# SCH_ESP32-S3-DevKitC-1_2026-10-10_1.net
KiCad netlist of a schematic drawn in EasyEDA
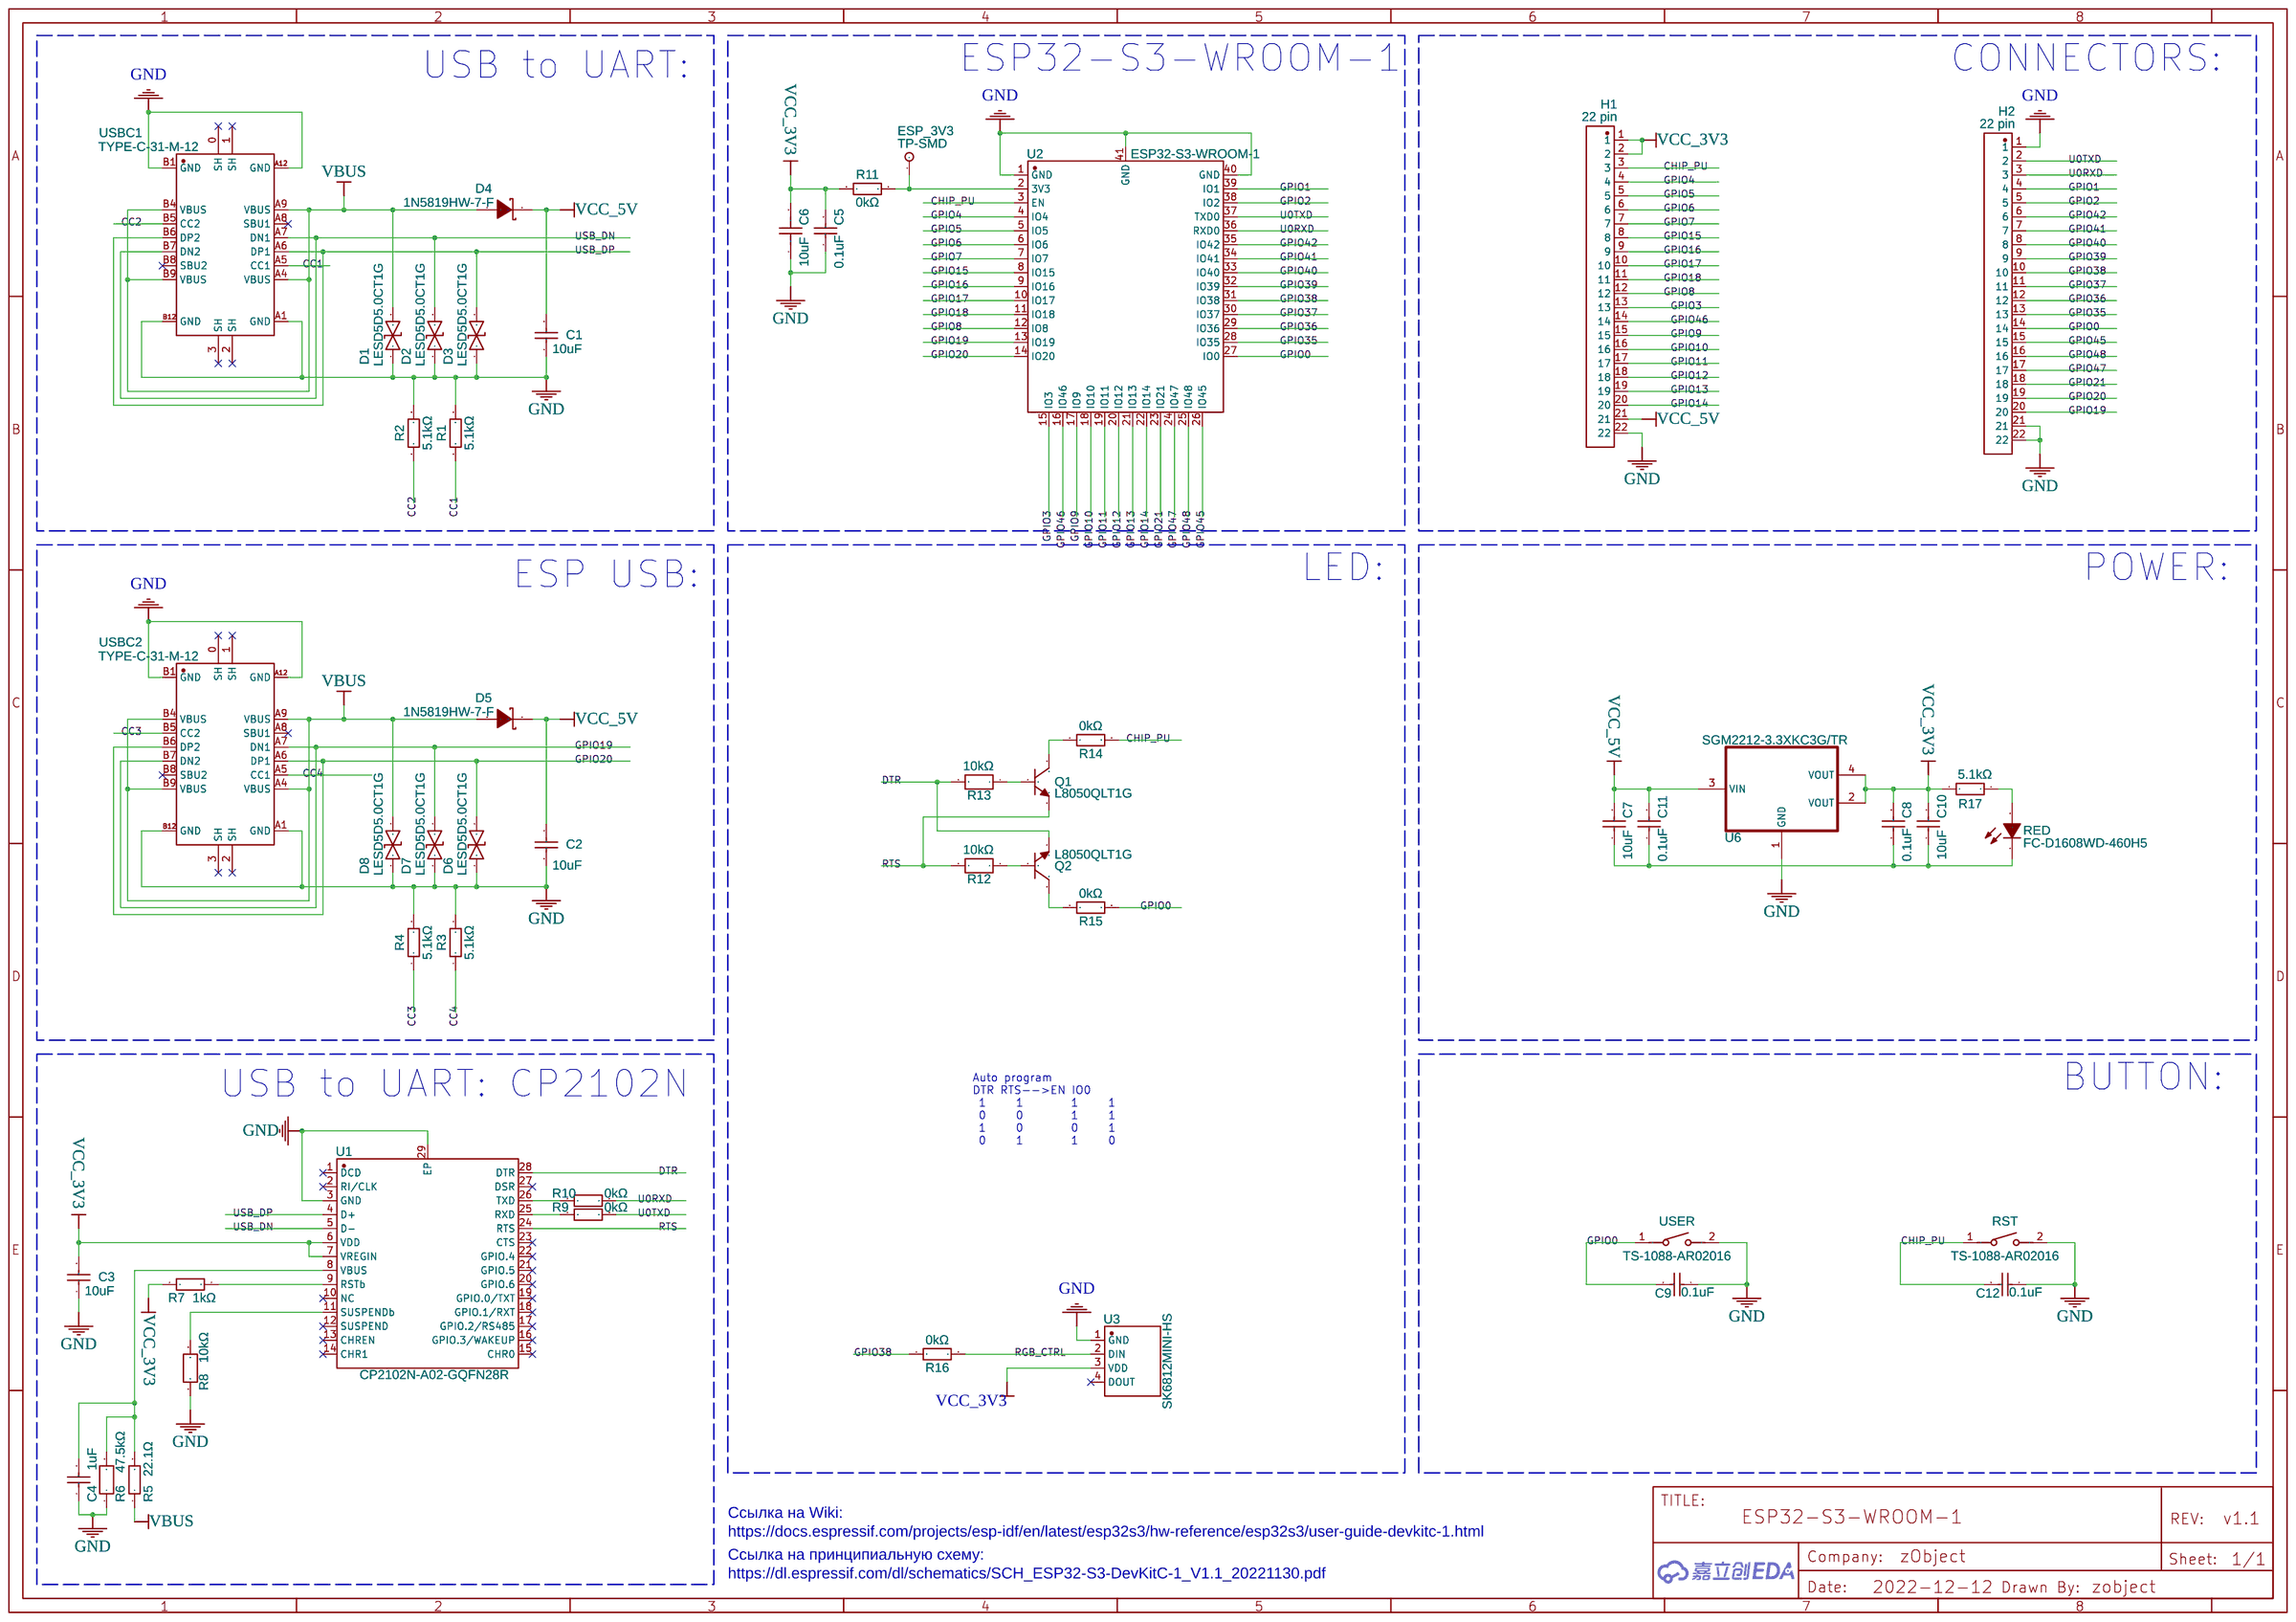
[diagram p0: schematic sheet]

(export (version "E")
  (design (tool "Eeschema 10.0.6"))
  (components
    (comp (ref "C1")
      (value "10uF")
      (fields (field (name "Manufacturer Part") "0603F106M160NT") (field (name "Manufacturer") "FH"))
      (libsource (lib "") (part "0603F106M160NT"))
    )
    (comp (ref "C2")
      (value "10uF")
      (fields (field (name "Manufacturer Part") "0603F106M160NT") (field (name "Manufacturer") "FH"))
      (libsource (lib "") (part "0603F106M160NT"))
    )
    (comp (ref "C3")
      (value "10uF")
      (fields (field (name "Manufacturer Part") "0603F106M160NT") (field (name "Manufacturer") "FH"))
      (libsource (lib "") (part "0603F106M160NT"))
    )
    (comp (ref "C4")
      (value "1uF")
      (fields (field (name "Manufacturer Part") "C1608X5R1C105KT000N") (field (name "Manufacturer") "TDK"))
      (libsource (lib "") (part "C1608X5R1C105KT000N"))
    )
    (comp (ref "C5")
      (value "0.1uF")
      (fields (field (name "Manufacturer Part") "0603B104K500NT") (field (name "Manufacturer") "FH(风华)"))
      (libsource (lib "") (part "0603B104K500NT"))
    )
    (comp (ref "C6")
      (value "10uF")
      (fields
        (field (name "Manufacturer Part") "LMK107BJ106MALTD")
        (field (name "Manufacturer") "TAIYO YUDEN")
      )
      (libsource (lib "") (part "LMK107BJ106MALTD"))
    )
    (comp (ref "C7")
      (value "10uF")
      (fields (field (name "Manufacturer Part") "0603F106M160NT") (field (name "Manufacturer") "FH"))
      (libsource (lib "") (part "0603F106M160NT"))
    )
    (comp (ref "C8")
      (value "0.1uF")
      (fields (field (name "Manufacturer Part") "0603B104K500NT") (field (name "Manufacturer") "FH(风华)"))
      (libsource (lib "") (part "0603B104K500NT"))
    )
    (comp (ref "C9")
      (value "0.1uF")
      (fields (field (name "Manufacturer Part") "0603B104K500NT") (field (name "Manufacturer") "FH(风华)"))
      (libsource (lib "") (part "0603B104K500NT_1"))
    )
    (comp (ref "C10")
      (value "10uF")
      (fields (field (name "Manufacturer Part") "0603F106M160NT") (field (name "Manufacturer") "FH"))
      (libsource (lib "") (part "0603F106M160NT"))
    )
    (comp (ref "C11")
      (value "0.1uF")
      (fields (field (name "Manufacturer Part") "0603B104K500NT") (field (name "Manufacturer") "FH(风华)"))
      (libsource (lib "") (part "0603B104K500NT"))
    )
    (comp (ref "C12")
      (value "0.1uF")
      (fields (field (name "Manufacturer Part") "0603B104K500NT") (field (name "Manufacturer") "FH(风华)"))
      (libsource (lib "") (part "0603B104K500NT_1"))
    )
    (comp (ref "D1")
      (value "LESD5D5.0CT1G")
      (fields (field (name "Manufacturer") "Leshan Radio"))
      (libsource (lib "") (part "LESD5D5.0CT1G"))
    )
    (comp (ref "D2")
      (value "LESD5D5.0CT1G")
      (fields (field (name "Manufacturer") "Leshan Radio"))
      (libsource (lib "") (part "LESD5D5.0CT1G"))
    )
    (comp (ref "D3")
      (value "LESD5D5.0CT1G")
      (fields (field (name "Manufacturer") "Leshan Radio"))
      (libsource (lib "") (part "LESD5D5.0CT1G"))
    )
    (comp (ref "D4")
      (value "1N5819HW-7-F")
      (fields (field (name "Manufacturer") "DIODES(美台)"))
      (libsource (lib "") (part "1N5819HW-7-F"))
    )
    (comp (ref "D5")
      (value "1N5819HW-7-F")
      (fields (field (name "Manufacturer") "DIODES(美台)"))
      (libsource (lib "") (part "1N5819HW-7-F"))
    )
    (comp (ref "D6")
      (value "LESD5D5.0CT1G")
      (fields (field (name "Manufacturer") "Leshan Radio"))
      (libsource (lib "") (part "LESD5D5.0CT1G"))
    )
    (comp (ref "D7")
      (value "LESD5D5.0CT1G")
      (fields (field (name "Manufacturer") "Leshan Radio"))
      (libsource (lib "") (part "LESD5D5.0CT1G"))
    )
    (comp (ref "D8")
      (value "LESD5D5.0CT1G")
      (fields (field (name "Manufacturer") "Leshan Radio"))
      (libsource (lib "") (part "LESD5D5.0CT1G"))
    )
    (comp (ref "ESP_3V3") (value "TP-SMD") (libsource (lib "") (part "TP-SMD")))
    (comp (ref "H1")
      (value "22 pin")
      (fields (field (name "Manufacturer Part") "22850120ANG1SYA01") (field (name "Manufacturer") "JILN(锦凌)"))
      (libsource (lib "") (part "22 pin"))
    )
    (comp (ref "H2")
      (value "22 pin")
      (fields (field (name "Manufacturer Part") "22850120ANG1SYA01") (field (name "Manufacturer") "JILN(锦凌)"))
      (libsource (lib "") (part "22 pin"))
    )
    (comp (ref "Q1")
      (value "L8050QLT1G")
      (fields (field (name "Manufacturer") "LRC(乐山无线电)"))
      (libsource (lib "") (part "L8050QLT1G_1"))
    )
    (comp (ref "Q2")
      (value "L8050QLT1G")
      (fields (field (name "Manufacturer") "LRC(乐山无线电)"))
      (libsource (lib "") (part "L8050QLT1G"))
    )
    (comp (ref "R1")
      (value "5.1kΩ")
      (fields (field (name "Manufacturer Part") "RTT035101BTP") (field (name "Manufacturer") "RALEC(旺诠)"))
      (libsource (lib "") (part "RTT035101BTP"))
    )
    (comp (ref "R2")
      (value "5.1kΩ")
      (fields (field (name "Manufacturer Part") "RTT035101BTP") (field (name "Manufacturer") "RALEC(旺诠)"))
      (libsource (lib "") (part "RTT035101BTP"))
    )
    (comp (ref "R3")
      (value "5.1kΩ")
      (fields (field (name "Manufacturer Part") "RTT035101BTP") (field (name "Manufacturer") "RALEC(旺诠)"))
      (libsource (lib "") (part "RTT035101BTP"))
    )
    (comp (ref "R4")
      (value "5.1kΩ")
      (fields (field (name "Manufacturer Part") "RTT035101BTP") (field (name "Manufacturer") "RALEC(旺诠)"))
      (libsource (lib "") (part "RTT035101BTP"))
    )
    (comp (ref "R5")
      (value "22.1Ω")
      (fields (field (name "Manufacturer Part") "RCT0322R1FLF") (field (name "Manufacturer") "HKR"))
      (libsource (lib "") (part "RCT0322R1FLF"))
    )
    (comp (ref "R6")
      (value "47.5kΩ")
      (fields (field (name "Manufacturer Part") "ERJPB3B4752V") (field (name "Manufacturer") "PANASONIC(松下)"))
      (libsource (lib "") (part "ERJPB3B4752V"))
    )
    (comp (ref "R7")
      (value "1kΩ")
      (fields (field (name "Manufacturer Part") "RN73H1JTTD1001B25") (field (name "Manufacturer") "KOA"))
      (libsource (lib "") (part "RN73H1JTTD1001B25"))
    )
    (comp (ref "R8")
      (value "10kΩ")
      (fields (field (name "Manufacturer Part") "CR-03JA7---10K") (field (name "Manufacturer") "Viking(光颉)"))
      (libsource (lib "") (part "CR-03JA7---10K_1"))
    )
    (comp (ref "R9")
      (value "0kΩ")
      (fields (field (name "Manufacturer Part") "RN73H1JTTD1001B25") (field (name "Manufacturer") "KOA"))
      (libsource (lib "") (part "RN73H1JTTD1001B25"))
    )
    (comp (ref "R10")
      (value "0kΩ")
      (fields (field (name "Manufacturer Part") "RN73H1JTTD1001B25") (field (name "Manufacturer") "KOA"))
      (libsource (lib "") (part "RN73H1JTTD1001B25"))
    )
    (comp (ref "R11")
      (value "0kΩ")
      (fields (field (name "Manufacturer Part") "RN73H1JTTD1001B25") (field (name "Manufacturer") "KOA"))
      (libsource (lib "") (part "RN73H1JTTD1001B25"))
    )
    (comp (ref "R12")
      (value "10kΩ")
      (fields (field (name "Manufacturer Part") "CR-03JA7---10K") (field (name "Manufacturer") "Viking(光颉)"))
      (libsource (lib "") (part "CR-03JA7---10K"))
    )
    (comp (ref "R13")
      (value "10kΩ")
      (fields (field (name "Manufacturer Part") "CR-03JA7---10K") (field (name "Manufacturer") "Viking(光颉)"))
      (libsource (lib "") (part "CR-03JA7---10K"))
    )
    (comp (ref "R14")
      (value "0kΩ")
      (fields (field (name "Manufacturer Part") "RN73H1JTTD1001B25") (field (name "Manufacturer") "KOA"))
      (libsource (lib "") (part "RN73H1JTTD1001B25"))
    )
    (comp (ref "R15")
      (value "0kΩ")
      (fields (field (name "Manufacturer Part") "RN73H1JTTD1001B25") (field (name "Manufacturer") "KOA"))
      (libsource (lib "") (part "RN73H1JTTD1001B25"))
    )
    (comp (ref "R16")
      (value "0kΩ")
      (fields (field (name "Manufacturer Part") "RN73H1JTTD1001B25") (field (name "Manufacturer") "KOA"))
      (libsource (lib "") (part "RN73H1JTTD1001B25"))
    )
    (comp (ref "R17")
      (value "5.1kΩ")
      (fields (field (name "Manufacturer Part") "RTT035101BTP") (field (name "Manufacturer") "RALEC(旺诠)"))
      (libsource (lib "") (part "RTT035101BTP_1"))
    )
    (comp (ref "RED")
      (value "FC-D1608WD-460H5")
      (fields (field (name "Manufacturer Part") "NCD0603W1") (field (name "Manufacturer") "国星光电"))
      (libsource (lib "") (part "FC-D1608WD-460H5"))
    )
    (comp (ref "RST")
      (value "TS-1088-AR02016")
      (fields (field (name "Manufacturer") "XUNPU(讯普)"))
      (libsource (lib "") (part "TS-1088-AR02016"))
    )
    (comp (ref "U1")
      (value "CP2102N-A02-GQFN28R")
      (fields (field (name "Manufacturer") "SILICON LABS(芯科)"))
      (libsource (lib "") (part "CP2102N-A02-GQFN28R"))
    )
    (comp (ref "U2")
      (value "ESP32-S3-WROOM-1")
      (fields
        (field (name "Manufacturer Part") "ESP32-S3-WROOM-1(N8R8)")
        (field (name "Manufacturer") "ESPRESSIF(乐鑫)")
      )
      (libsource (lib "") (part "ESP32-S3-WROOM-1(N8R8)"))
    )
    (comp (ref "U3") (value "SK6812MINI-HS") (libsource (lib "") (part "SK6812MINI-HS")))
    (comp (ref "U6") (value "SGM2212-3.3XKC3G/TR") (libsource (lib "") (part "SGM2212-3.3XKC3G/TR")))
    (comp (ref "USBC1")
      (value "TYPE-C-31-M-12")
      (fields (field (name "Manufacturer") "韩国韩荣"))
      (libsource (lib "") (part "TYPE-C-31-M-12"))
    )
    (comp (ref "USBC2")
      (value "TYPE-C-31-M-12")
      (fields (field (name "Manufacturer") "韩国韩荣"))
      (libsource (lib "") (part "TYPE-C-31-M-12"))
    )
    (comp (ref "USER")
      (value "TS-1088-AR02016")
      (fields (field (name "Manufacturer") "XUNPU(讯普)"))
      (libsource (lib "") (part "TS-1088-AR02016_1"))
    )
  )
  (nets
    (net (code "1") (name "/CC1") (class "Default")
      (node (ref "R1") (pin "1") (pinfunction "1_1") (pintype "unspecified"))
      (node (ref "USBC1") (pin "A5") (pinfunction "CC1_A5") (pintype "unspecified"))
    )
    (net (code "2") (name "/CC2") (class "Default")
      (node (ref "R2") (pin "1") (pinfunction "1_1") (pintype "unspecified"))
      (node (ref "USBC1") (pin "B5") (pinfunction "CC2_B5") (pintype "unspecified"))
    )
    (net (code "3") (name "/CC3") (class "Default")
      (node (ref "R4") (pin "1") (pinfunction "1_1") (pintype "unspecified"))
      (node (ref "USBC2") (pin "B5") (pinfunction "CC2_B5") (pintype "unspecified"))
    )
    (net (code "4") (name "/CC4") (class "Default")
      (node (ref "R3") (pin "1") (pinfunction "1_1") (pintype "unspecified"))
      (node (ref "USBC2") (pin "A5") (pinfunction "CC1_A5") (pintype "unspecified"))
    )
    (net (code "5") (name "/CHIP_PU") (class "Default")
      (node (ref "C12") (pin "2") (pinfunction "2_2") (pintype "input"))
      (node (ref "H1") (pin "3") (pinfunction "3_3") (pintype "unspecified"))
      (node (ref "R14") (pin "2") (pinfunction "2_2") (pintype "unspecified"))
      (node (ref "RST") (pin "1") (pinfunction "1_1") (pintype "unspecified"))
      (node (ref "U2") (pin "3") (pinfunction "EN_3") (pintype "unspecified"))
    )
    (net (code "6") (name "/DTR") (class "Default")
      (node (ref "Q2") (pin "2") (pinfunction "E_2") (pintype "unspecified"))
      (node (ref "R13") (pin "2") (pinfunction "2_2") (pintype "unspecified"))
      (node (ref "U1") (pin "28") (pinfunction "DTR_28") (pintype "unspecified"))
    )
    (net (code "7") (name "/GPIO0") (class "Default")
      (node (ref "C9") (pin "2") (pinfunction "2_2") (pintype "input"))
      (node (ref "H2") (pin "14") (pinfunction "14_14") (pintype "unspecified"))
      (node (ref "R15") (pin "2") (pinfunction "2_2") (pintype "unspecified"))
      (node (ref "U2") (pin "27") (pinfunction "IO0_27") (pintype "unspecified"))
      (node (ref "USER") (pin "1") (pinfunction "1_1") (pintype "unspecified"))
    )
    (net (code "8") (name "/GPIO1") (class "Default")
      (node (ref "H2") (pin "4") (pinfunction "4_4") (pintype "unspecified"))
      (node (ref "U2") (pin "39") (pinfunction "IO1_39") (pintype "unspecified"))
    )
    (net (code "9") (name "/GPIO2") (class "Default")
      (node (ref "H2") (pin "5") (pinfunction "5_5") (pintype "unspecified"))
      (node (ref "U2") (pin "38") (pinfunction "IO2_38") (pintype "unspecified"))
    )
    (net (code "10") (name "/GPIO3") (class "Default")
      (node (ref "H1") (pin "13") (pinfunction "13_13") (pintype "unspecified"))
      (node (ref "U2") (pin "15") (pinfunction "IO3_15") (pintype "unspecified"))
    )
    (net (code "11") (name "/GPIO4") (class "Default")
      (node (ref "H1") (pin "4") (pinfunction "4_4") (pintype "unspecified"))
      (node (ref "U2") (pin "4") (pinfunction "IO4_4") (pintype "unspecified"))
    )
    (net (code "12") (name "/GPIO5") (class "Default")
      (node (ref "H1") (pin "5") (pinfunction "5_5") (pintype "unspecified"))
      (node (ref "U2") (pin "5") (pinfunction "IO5_5") (pintype "unspecified"))
    )
    (net (code "13") (name "/GPIO6") (class "Default")
      (node (ref "H1") (pin "6") (pinfunction "6_6") (pintype "unspecified"))
      (node (ref "U2") (pin "6") (pinfunction "IO6_6") (pintype "unspecified"))
    )
    (net (code "14") (name "/GPIO7") (class "Default")
      (node (ref "H1") (pin "7") (pinfunction "7_7") (pintype "unspecified"))
      (node (ref "U2") (pin "7") (pinfunction "IO7_7") (pintype "unspecified"))
    )
    (net (code "15") (name "/GPIO8") (class "Default")
      (node (ref "H1") (pin "12") (pinfunction "12_12") (pintype "unspecified"))
      (node (ref "U2") (pin "12") (pinfunction "IO8_12") (pintype "unspecified"))
    )
    (net (code "16") (name "/GPIO9") (class "Default")
      (node (ref "H1") (pin "15") (pinfunction "15_15") (pintype "unspecified"))
      (node (ref "U2") (pin "17") (pinfunction "IO9_17") (pintype "unspecified"))
    )
    (net (code "17") (name "/GPIO10") (class "Default")
      (node (ref "H1") (pin "16") (pinfunction "16_16") (pintype "unspecified"))
      (node (ref "U2") (pin "18") (pinfunction "IO10_18") (pintype "unspecified"))
    )
    (net (code "18") (name "/GPIO11") (class "Default")
      (node (ref "H1") (pin "17") (pinfunction "17_17") (pintype "unspecified"))
      (node (ref "U2") (pin "19") (pinfunction "IO11_19") (pintype "unspecified"))
    )
    (net (code "19") (name "/GPIO12") (class "Default")
      (node (ref "H1") (pin "18") (pinfunction "18_18") (pintype "unspecified"))
      (node (ref "U2") (pin "20") (pinfunction "IO12_20") (pintype "unspecified"))
    )
    (net (code "20") (name "/GPIO13") (class "Default")
      (node (ref "H1") (pin "19") (pinfunction "19_19") (pintype "unspecified"))
      (node (ref "U2") (pin "21") (pinfunction "IO13_21") (pintype "unspecified"))
    )
    (net (code "21") (name "/GPIO14") (class "Default")
      (node (ref "H1") (pin "20") (pinfunction "20_20") (pintype "unspecified"))
      (node (ref "U2") (pin "22") (pinfunction "IO14_22") (pintype "unspecified"))
    )
    (net (code "22") (name "/GPIO15") (class "Default")
      (node (ref "H1") (pin "8") (pinfunction "8_8") (pintype "unspecified"))
      (node (ref "U2") (pin "8") (pinfunction "IO15_8") (pintype "unspecified"))
    )
    (net (code "23") (name "/GPIO16") (class "Default")
      (node (ref "H1") (pin "9") (pinfunction "9_9") (pintype "unspecified"))
      (node (ref "U2") (pin "9") (pinfunction "IO16_9") (pintype "unspecified"))
    )
    (net (code "24") (name "/GPIO17") (class "Default")
      (node (ref "H1") (pin "10") (pinfunction "10_10") (pintype "unspecified"))
      (node (ref "U2") (pin "10") (pinfunction "IO17_10") (pintype "unspecified"))
    )
    (net (code "25") (name "/GPIO18") (class "Default")
      (node (ref "H1") (pin "11") (pinfunction "11_11") (pintype "unspecified"))
      (node (ref "U2") (pin "11") (pinfunction "IO18_11") (pintype "unspecified"))
    )
    (net (code "26") (name "/GPIO19") (class "Default")
      (node (ref "D7") (pin "2") (pinfunction "2_2") (pintype "unspecified"))
      (node (ref "H2") (pin "20") (pinfunction "20_20") (pintype "unspecified"))
      (node (ref "U2") (pin "13") (pinfunction "IO19_13") (pintype "unspecified"))
      (node (ref "USBC2") (pin "A7") (pinfunction "DN1_A7") (pintype "unspecified"))
      (node (ref "USBC2") (pin "B7") (pinfunction "DN2_B7") (pintype "unspecified"))
    )
    (net (code "27") (name "/GPIO20") (class "Default")
      (node (ref "D6") (pin "2") (pinfunction "2_2") (pintype "unspecified"))
      (node (ref "H2") (pin "19") (pinfunction "19_19") (pintype "unspecified"))
      (node (ref "U2") (pin "14") (pinfunction "IO20_14") (pintype "unspecified"))
      (node (ref "USBC2") (pin "A6") (pinfunction "DP1_A6") (pintype "unspecified"))
      (node (ref "USBC2") (pin "B6") (pinfunction "DP2_B6") (pintype "unspecified"))
    )
    (net (code "28") (name "/GPIO21") (class "Default")
      (node (ref "H2") (pin "18") (pinfunction "18_18") (pintype "unspecified"))
      (node (ref "U2") (pin "23") (pinfunction "IO21_23") (pintype "unspecified"))
    )
    (net (code "29") (name "/GPIO35") (class "Default")
      (node (ref "H2") (pin "13") (pinfunction "13_13") (pintype "unspecified"))
      (node (ref "U2") (pin "28") (pinfunction "IO35_28") (pintype "unspecified"))
    )
    (net (code "30") (name "/GPIO36") (class "Default")
      (node (ref "H2") (pin "12") (pinfunction "12_12") (pintype "unspecified"))
      (node (ref "U2") (pin "29") (pinfunction "IO36_29") (pintype "unspecified"))
    )
    (net (code "31") (name "/GPIO37") (class "Default")
      (node (ref "H2") (pin "11") (pinfunction "11_11") (pintype "unspecified"))
      (node (ref "U2") (pin "30") (pinfunction "IO37_30") (pintype "unspecified"))
    )
    (net (code "32") (name "/GPIO38") (class "Default")
      (node (ref "H2") (pin "10") (pinfunction "10_10") (pintype "unspecified"))
      (node (ref "R16") (pin "1") (pinfunction "1_1") (pintype "unspecified"))
      (node (ref "U2") (pin "31") (pinfunction "IO38_31") (pintype "unspecified"))
    )
    (net (code "33") (name "/GPIO39") (class "Default")
      (node (ref "H2") (pin "9") (pinfunction "9_9") (pintype "unspecified"))
      (node (ref "U2") (pin "32") (pinfunction "IO39_32") (pintype "unspecified"))
    )
    (net (code "34") (name "/GPIO40") (class "Default")
      (node (ref "H2") (pin "8") (pinfunction "8_8") (pintype "unspecified"))
      (node (ref "U2") (pin "33") (pinfunction "IO40_33") (pintype "unspecified"))
    )
    (net (code "35") (name "/GPIO41") (class "Default")
      (node (ref "H2") (pin "7") (pinfunction "7_7") (pintype "unspecified"))
      (node (ref "U2") (pin "34") (pinfunction "IO41_34") (pintype "unspecified"))
    )
    (net (code "36") (name "/GPIO42") (class "Default")
      (node (ref "H2") (pin "6") (pinfunction "6_6") (pintype "unspecified"))
      (node (ref "U2") (pin "35") (pinfunction "IO42_35") (pintype "unspecified"))
    )
    (net (code "37") (name "/GPIO45") (class "Default")
      (node (ref "H2") (pin "15") (pinfunction "15_15") (pintype "unspecified"))
      (node (ref "U2") (pin "26") (pinfunction "IO45_26") (pintype "unspecified"))
    )
    (net (code "38") (name "/GPIO46") (class "Default")
      (node (ref "H1") (pin "14") (pinfunction "14_14") (pintype "unspecified"))
      (node (ref "U2") (pin "16") (pinfunction "IO46_16") (pintype "unspecified"))
    )
    (net (code "39") (name "/GPIO47") (class "Default")
      (node (ref "H2") (pin "17") (pinfunction "17_17") (pintype "unspecified"))
      (node (ref "U2") (pin "24") (pinfunction "IO47_24") (pintype "unspecified"))
    )
    (net (code "40") (name "/GPIO48") (class "Default")
      (node (ref "H2") (pin "16") (pinfunction "16_16") (pintype "unspecified"))
      (node (ref "U2") (pin "25") (pinfunction "IO48_25") (pintype "unspecified"))
    )
    (net (code "41") (name "/RGB_CTRL") (class "Default")
      (node (ref "R16") (pin "2") (pinfunction "2_2") (pintype "unspecified"))
      (node (ref "U3") (pin "2") (pinfunction "DIN_2") (pintype "unspecified"))
    )
    (net (code "42") (name "/RTS") (class "Default")
      (node (ref "Q1") (pin "2") (pinfunction "E_2") (pintype "unspecified"))
      (node (ref "R12") (pin "2") (pinfunction "2_2") (pintype "unspecified"))
      (node (ref "U1") (pin "24") (pinfunction "RTS_24") (pintype "unspecified"))
    )
    (net (code "43") (name "/U0RXD") (class "Default")
      (node (ref "H2") (pin "3") (pinfunction "3_3") (pintype "unspecified"))
      (node (ref "R10") (pin "2") (pinfunction "2_2") (pintype "unspecified"))
      (node (ref "U2") (pin "36") (pinfunction "RXD0_36") (pintype "unspecified"))
    )
    (net (code "44") (name "/U0TXD") (class "Default")
      (node (ref "H2") (pin "2") (pinfunction "2_2") (pintype "unspecified"))
      (node (ref "R9") (pin "2") (pinfunction "2_2") (pintype "unspecified"))
      (node (ref "U2") (pin "37") (pinfunction "TXD0_37") (pintype "unspecified"))
    )
    (net (code "45") (name "/USB_DN") (class "Default")
      (node (ref "D2") (pin "2") (pinfunction "2_2") (pintype "unspecified"))
      (node (ref "U1") (pin "5") (pinfunction "D-_5") (pintype "unspecified"))
      (node (ref "USBC1") (pin "A7") (pinfunction "DN1_A7") (pintype "unspecified"))
      (node (ref "USBC1") (pin "B7") (pinfunction "DN2_B7") (pintype "unspecified"))
    )
    (net (code "46") (name "/USB_DP") (class "Default")
      (node (ref "D3") (pin "2") (pinfunction "2_2") (pintype "unspecified"))
      (node (ref "U1") (pin "4") (pinfunction "D+_4") (pintype "unspecified"))
      (node (ref "USBC1") (pin "A6") (pinfunction "DP1_A6") (pintype "unspecified"))
      (node (ref "USBC1") (pin "B6") (pinfunction "DP2_B6") (pintype "unspecified"))
    )
    (net (code "47") (name "GND") (class "Default")
      (node (ref "C1") (pin "1") (pinfunction "1_1") (pintype "input"))
      (node (ref "C10") (pin "1") (pinfunction "1_1") (pintype "input"))
      (node (ref "C11") (pin "1") (pinfunction "1_1") (pintype "input"))
      (node (ref "C12") (pin "1") (pinfunction "1_1") (pintype "input"))
      (node (ref "C2") (pin "1") (pinfunction "1_1") (pintype "input"))
      (node (ref "C3") (pin "1") (pinfunction "1_1") (pintype "input"))
      (node (ref "C4") (pin "1") (pinfunction "1_1") (pintype "input"))
      (node (ref "C5") (pin "1") (pinfunction "1_1") (pintype "input"))
      (node (ref "C6") (pin "1") (pinfunction "1_1") (pintype "unspecified"))
      (node (ref "C7") (pin "1") (pinfunction "1_1") (pintype "input"))
      (node (ref "C8") (pin "1") (pinfunction "1_1") (pintype "input"))
      (node (ref "C9") (pin "1") (pinfunction "1_1") (pintype "input"))
      (node (ref "D1") (pin "1") (pinfunction "1_1") (pintype "unspecified"))
      (node (ref "D2") (pin "1") (pinfunction "1_1") (pintype "unspecified"))
      (node (ref "D3") (pin "1") (pinfunction "1_1") (pintype "unspecified"))
      (node (ref "D6") (pin "1") (pinfunction "1_1") (pintype "unspecified"))
      (node (ref "D7") (pin "1") (pinfunction "1_1") (pintype "unspecified"))
      (node (ref "D8") (pin "1") (pinfunction "1_1") (pintype "unspecified"))
      (node (ref "H1") (pin "22") (pinfunction "22_22") (pintype "unspecified"))
      (node (ref "H2") (pin "1") (pinfunction "1_1") (pintype "unspecified"))
      (node (ref "H2") (pin "21") (pinfunction "21_21") (pintype "unspecified"))
      (node (ref "H2") (pin "22") (pinfunction "22_22") (pintype "unspecified"))
      (node (ref "R1") (pin "2") (pinfunction "2_2") (pintype "unspecified"))
      (node (ref "R2") (pin "2") (pinfunction "2_2") (pintype "unspecified"))
      (node (ref "R3") (pin "2") (pinfunction "2_2") (pintype "unspecified"))
      (node (ref "R4") (pin "2") (pinfunction "2_2") (pintype "unspecified"))
      (node (ref "R6") (pin "1") (pinfunction "1_1") (pintype "unspecified"))
      (node (ref "R8") (pin "1") (pinfunction "1_1") (pintype "unspecified"))
      (node (ref "RED") (pin "1") (pinfunction "-_1") (pintype "input"))
      (node (ref "RST") (pin "2") (pinfunction "2_2") (pintype "unspecified"))
      (node (ref "U1") (pin "29") (pinfunction "EP_29") (pintype "unspecified"))
      (node (ref "U1") (pin "3") (pinfunction "GND_3") (pintype "unspecified"))
      (node (ref "U2") (pin "1") (pinfunction "GND_1") (pintype "unspecified"))
      (node (ref "U2") (pin "40") (pinfunction "GND_40") (pintype "unspecified"))
      (node (ref "U2") (pin "41") (pinfunction "GND_41") (pintype "unspecified"))
      (node (ref "U3") (pin "1") (pinfunction "GND_1") (pintype "unspecified"))
      (node (ref "U6") (pin "1") (pinfunction "GND_1") (pintype "unspecified"))
      (node (ref "USBC1") (pin "A1") (pinfunction "GND_A1") (pintype "unspecified"))
      (node (ref "USBC1") (pin "A12") (pinfunction "GND_A12") (pintype "unspecified"))
      (node (ref "USBC1") (pin "B1") (pinfunction "GND_B1") (pintype "unspecified"))
      (node (ref "USBC1") (pin "B12") (pinfunction "GND_B12") (pintype "unspecified"))
      (node (ref "USBC2") (pin "A1") (pinfunction "GND_A1") (pintype "unspecified"))
      (node (ref "USBC2") (pin "A12") (pinfunction "GND_A12") (pintype "unspecified"))
      (node (ref "USBC2") (pin "B1") (pinfunction "GND_B1") (pintype "unspecified"))
      (node (ref "USBC2") (pin "B12") (pinfunction "GND_B12") (pintype "unspecified"))
      (node (ref "USER") (pin "2") (pinfunction "2_2") (pintype "unspecified"))
    )
    (net (code "48") (name "Net-(Q1-B)") (class "Default")
      (node (ref "Q1") (pin "1") (pinfunction "B_1") (pintype "unspecified"))
      (node (ref "R13") (pin "1") (pinfunction "1_1") (pintype "unspecified"))
    )
    (net (code "49") (name "Net-(Q1-C)") (class "Default")
      (node (ref "Q1") (pin "3") (pinfunction "C_3") (pintype "unspecified"))
      (node (ref "R14") (pin "1") (pinfunction "1_1") (pintype "unspecified"))
    )
    (net (code "50") (name "Net-(Q2-B)") (class "Default")
      (node (ref "Q2") (pin "1") (pinfunction "B_1") (pintype "unspecified"))
      (node (ref "R12") (pin "1") (pinfunction "1_1") (pintype "unspecified"))
    )
    (net (code "51") (name "Net-(Q2-C)") (class "Default")
      (node (ref "Q2") (pin "3") (pinfunction "C_3") (pintype "unspecified"))
      (node (ref "R15") (pin "1") (pinfunction "1_1") (pintype "unspecified"))
    )
    (net (code "52") (name "Net-(RED-+)") (class "Default")
      (node (ref "R17") (pin "1") (pinfunction "1_1") (pintype "unspecified"))
      (node (ref "RED") (pin "2") (pinfunction "+_2") (pintype "input"))
    )
    (net (code "53") (name "Net-(U1-RSTb)") (class "Default")
      (node (ref "R7") (pin "2") (pinfunction "2_2") (pintype "unspecified"))
      (node (ref "U1") (pin "9") (pinfunction "RSTb_9") (pintype "unspecified"))
    )
    (net (code "54") (name "Net-(U1-RXD)") (class "Default")
      (node (ref "R9") (pin "1") (pinfunction "1_1") (pintype "unspecified"))
      (node (ref "U1") (pin "25") (pinfunction "RXD_25") (pintype "unspecified"))
    )
    (net (code "55") (name "Net-(U1-SUSPENDb)") (class "Default")
      (node (ref "R8") (pin "2") (pinfunction "2_2") (pintype "unspecified"))
      (node (ref "U1") (pin "11") (pinfunction "SUSPENDb_11") (pintype "unspecified"))
    )
    (net (code "56") (name "Net-(U1-TXD)") (class "Default")
      (node (ref "R10") (pin "1") (pinfunction "1_1") (pintype "unspecified"))
      (node (ref "U1") (pin "26") (pinfunction "TXD_26") (pintype "unspecified"))
    )
    (net (code "57") (name "Net-(U1-VBUS)") (class "Default")
      (node (ref "C4") (pin "2") (pinfunction "2_2") (pintype "input"))
      (node (ref "R5") (pin "2") (pinfunction "2_2") (pintype "unspecified"))
      (node (ref "R6") (pin "2") (pinfunction "2_2") (pintype "unspecified"))
      (node (ref "U1") (pin "8") (pinfunction "VBUS_8") (pintype "unspecified"))
    )
    (net (code "58") (name "Net-(U2-3V3)") (class "Default")
      (node (ref "ESP_3V3") (pin "1") (pinfunction "1_1") (pintype "unspecified"))
      (node (ref "R11") (pin "2") (pinfunction "2_2") (pintype "unspecified"))
      (node (ref "U2") (pin "2") (pinfunction "3V3_2") (pintype "unspecified"))
    )
    (net (code "59") (name "VBUS") (class "Default")
      (node (ref "D1") (pin "2") (pinfunction "2_2") (pintype "unspecified"))
      (node (ref "D4") (pin "1") (pinfunction "A_1") (pintype "unspecified"))
      (node (ref "D5") (pin "1") (pinfunction "A_1") (pintype "unspecified"))
      (node (ref "D8") (pin "2") (pinfunction "2_2") (pintype "unspecified"))
      (node (ref "R5") (pin "1") (pinfunction "1_1") (pintype "unspecified"))
      (node (ref "USBC1") (pin "A4") (pinfunction "VBUS_A4") (pintype "unspecified"))
      (node (ref "USBC1") (pin "A9") (pinfunction "VBUS_A9") (pintype "unspecified"))
      (node (ref "USBC1") (pin "B4") (pinfunction "VBUS_B4") (pintype "unspecified"))
      (node (ref "USBC1") (pin "B9") (pinfunction "VBUS_B9") (pintype "unspecified"))
      (node (ref "USBC2") (pin "A4") (pinfunction "VBUS_A4") (pintype "unspecified"))
      (node (ref "USBC2") (pin "A9") (pinfunction "VBUS_A9") (pintype "unspecified"))
      (node (ref "USBC2") (pin "B4") (pinfunction "VBUS_B4") (pintype "unspecified"))
      (node (ref "USBC2") (pin "B9") (pinfunction "VBUS_B9") (pintype "unspecified"))
    )
    (net (code "60") (name "VCC_3V3") (class "Default")
      (node (ref "C10") (pin "2") (pinfunction "2_2") (pintype "input"))
      (node (ref "C3") (pin "2") (pinfunction "2_2") (pintype "input"))
      (node (ref "C5") (pin "2") (pinfunction "2_2") (pintype "input"))
      (node (ref "C6") (pin "2") (pinfunction "2_2") (pintype "unspecified"))
      (node (ref "C8") (pin "2") (pinfunction "2_2") (pintype "input"))
      (node (ref "H1") (pin "1") (pinfunction "1_1") (pintype "unspecified"))
      (node (ref "H1") (pin "2") (pinfunction "2_2") (pintype "unspecified"))
      (node (ref "R11") (pin "1") (pinfunction "1_1") (pintype "unspecified"))
      (node (ref "R17") (pin "2") (pinfunction "2_2") (pintype "unspecified"))
      (node (ref "R7") (pin "1") (pinfunction "1_1") (pintype "unspecified"))
      (node (ref "U1") (pin "6") (pinfunction "VDD_6") (pintype "unspecified"))
      (node (ref "U1") (pin "7") (pinfunction "VREGIN_7") (pintype "unspecified"))
      (node (ref "U3") (pin "3") (pinfunction "VDD_3") (pintype "unspecified"))
      (node (ref "U6") (pin "2") (pinfunction "VOUT_2") (pintype "unspecified"))
      (node (ref "U6") (pin "4") (pinfunction "VOUT_4") (pintype "unspecified"))
    )
    (net (code "61") (name "VCC_5V") (class "Default")
      (node (ref "C1") (pin "2") (pinfunction "2_2") (pintype "input"))
      (node (ref "C11") (pin "2") (pinfunction "2_2") (pintype "input"))
      (node (ref "C2") (pin "2") (pinfunction "2_2") (pintype "input"))
      (node (ref "C7") (pin "2") (pinfunction "2_2") (pintype "input"))
      (node (ref "D4") (pin "2") (pinfunction "K_2") (pintype "unspecified"))
      (node (ref "D5") (pin "2") (pinfunction "K_2") (pintype "unspecified"))
      (node (ref "H1") (pin "21") (pinfunction "21_21") (pintype "unspecified"))
      (node (ref "U6") (pin "3") (pinfunction "VIN_3") (pintype "unspecified"))
    )
    (net (code "62") (name "unconnected-(U1-CHR0-Pad15)") (class "Default")
      (node (ref "U1") (pin "15") (pinfunction "CHR0_15") (pintype "unspecified+no_connect"))
    )
    (net (code "63") (name "unconnected-(U1-CHR1-Pad14)") (class "Default")
      (node (ref "U1") (pin "14") (pinfunction "CHR1_14") (pintype "unspecified+no_connect"))
    )
    (net (code "64") (name "unconnected-(U1-CHREN-Pad13)") (class "Default")
      (node (ref "U1") (pin "13") (pinfunction "CHREN_13") (pintype "unspecified+no_connect"))
    )
    (net (code "65") (name "unconnected-(U1-CTS-Pad23)") (class "Default")
      (node (ref "U1") (pin "23") (pinfunction "CTS_23") (pintype "unspecified+no_connect"))
    )
    (net (code "66") (name "unconnected-(U1-DCD-Pad1)") (class "Default")
      (node (ref "U1") (pin "1") (pinfunction "DCD_1") (pintype "unspecified+no_connect"))
    )
    (net (code "67") (name "unconnected-(U1-DSR-Pad27)") (class "Default")
      (node (ref "U1") (pin "27") (pinfunction "DSR_27") (pintype "unspecified+no_connect"))
    )
    (net (code "68") (name "unconnected-(U1-GPIO.0{slash}TXT-Pad19)") (class "Default")
      (node (ref "U1") (pin "19") (pinfunction "GPIO.0/TXT_19") (pintype "unspecified+no_connect"))
    )
    (net (code "69") (name "unconnected-(U1-GPIO.1{slash}RXT-Pad18)") (class "Default")
      (node (ref "U1") (pin "18") (pinfunction "GPIO.1/RXT_18") (pintype "unspecified+no_connect"))
    )
    (net (code "70") (name "unconnected-(U1-GPIO.2{slash}RS485-Pad17)") (class "Default")
      (node (ref "U1") (pin "17") (pinfunction "GPIO.2/RS485_17") (pintype "unspecified+no_connect"))
    )
    (net (code "71") (name "unconnected-(U1-GPIO.3{slash}WAKEUP-Pad16)") (class "Default")
      (node (ref "U1") (pin "16") (pinfunction "GPIO.3/WAKEUP_16") (pintype "unspecified+no_connect"))
    )
    (net (code "72") (name "unconnected-(U1-GPIO.4-Pad22)") (class "Default")
      (node (ref "U1") (pin "22") (pinfunction "GPIO.4_22") (pintype "unspecified+no_connect"))
    )
    (net (code "73") (name "unconnected-(U1-GPIO.5-Pad21)") (class "Default")
      (node (ref "U1") (pin "21") (pinfunction "GPIO.5_21") (pintype "unspecified+no_connect"))
    )
    (net (code "74") (name "unconnected-(U1-GPIO.6-Pad20)") (class "Default")
      (node (ref "U1") (pin "20") (pinfunction "GPIO.6_20") (pintype "unspecified+no_connect"))
    )
    (net (code "75") (name "unconnected-(U1-NC-Pad10)") (class "Default")
      (node (ref "U1") (pin "10") (pinfunction "NC_10") (pintype "unspecified+no_connect"))
    )
    (net (code "76") (name "unconnected-(U1-RI{slash}CLK-Pad2)") (class "Default")
      (node (ref "U1") (pin "2") (pinfunction "RI/CLK_2") (pintype "unspecified+no_connect"))
    )
    (net (code "77") (name "unconnected-(U1-SUSPEND-Pad12)") (class "Default")
      (node (ref "U1") (pin "12") (pinfunction "SUSPEND_12") (pintype "unspecified+no_connect"))
    )
    (net (code "78") (name "unconnected-(U3-DOUT-Pad4)") (class "Default")
      (node (ref "U3") (pin "4") (pinfunction "DOUT_4") (pintype "unspecified+no_connect"))
    )
    (net (code "79") (name "unconnected-(USBC1-SBU1-PadA8)") (class "Default")
      (node (ref "USBC1") (pin "A8") (pinfunction "SBU1_A8") (pintype "unspecified+no_connect"))
    )
    (net (code "80") (name "unconnected-(USBC1-SBU2-PadB8)") (class "Default")
      (node (ref "USBC1") (pin "B8") (pinfunction "SBU2_B8") (pintype "unspecified+no_connect"))
    )
    (net (code "81") (name "unconnected-(USBC1-SH-Pad0)") (class "Default")
      (node (ref "USBC1") (pin "0") (pinfunction "SH_0") (pintype "unspecified+no_connect"))
    )
    (net (code "82") (name "unconnected-(USBC1-SH-Pad1)") (class "Default")
      (node (ref "USBC1") (pin "1") (pinfunction "SH_1") (pintype "unspecified+no_connect"))
    )
    (net (code "83") (name "unconnected-(USBC1-SH-Pad2)") (class "Default")
      (node (ref "USBC1") (pin "2") (pinfunction "SH_2") (pintype "unspecified+no_connect"))
    )
    (net (code "84") (name "unconnected-(USBC1-SH-Pad3)") (class "Default")
      (node (ref "USBC1") (pin "3") (pinfunction "SH_3") (pintype "unspecified+no_connect"))
    )
    (net (code "85") (name "unconnected-(USBC2-SBU1-PadA8)") (class "Default")
      (node (ref "USBC2") (pin "A8") (pinfunction "SBU1_A8") (pintype "unspecified+no_connect"))
    )
    (net (code "86") (name "unconnected-(USBC2-SBU2-PadB8)") (class "Default")
      (node (ref "USBC2") (pin "B8") (pinfunction "SBU2_B8") (pintype "unspecified+no_connect"))
    )
    (net (code "87") (name "unconnected-(USBC2-SH-Pad0)") (class "Default")
      (node (ref "USBC2") (pin "0") (pinfunction "SH_0") (pintype "unspecified+no_connect"))
    )
    (net (code "88") (name "unconnected-(USBC2-SH-Pad1)") (class "Default")
      (node (ref "USBC2") (pin "1") (pinfunction "SH_1") (pintype "unspecified+no_connect"))
    )
    (net (code "89") (name "unconnected-(USBC2-SH-Pad2)") (class "Default")
      (node (ref "USBC2") (pin "2") (pinfunction "SH_2") (pintype "unspecified+no_connect"))
    )
    (net (code "90") (name "unconnected-(USBC2-SH-Pad3)") (class "Default")
      (node (ref "USBC2") (pin "3") (pinfunction "SH_3") (pintype "unspecified+no_connect"))
    )
  )
)
